# PLC1_3.net
KiCad netlist of a schematic drawn in Altium Designer
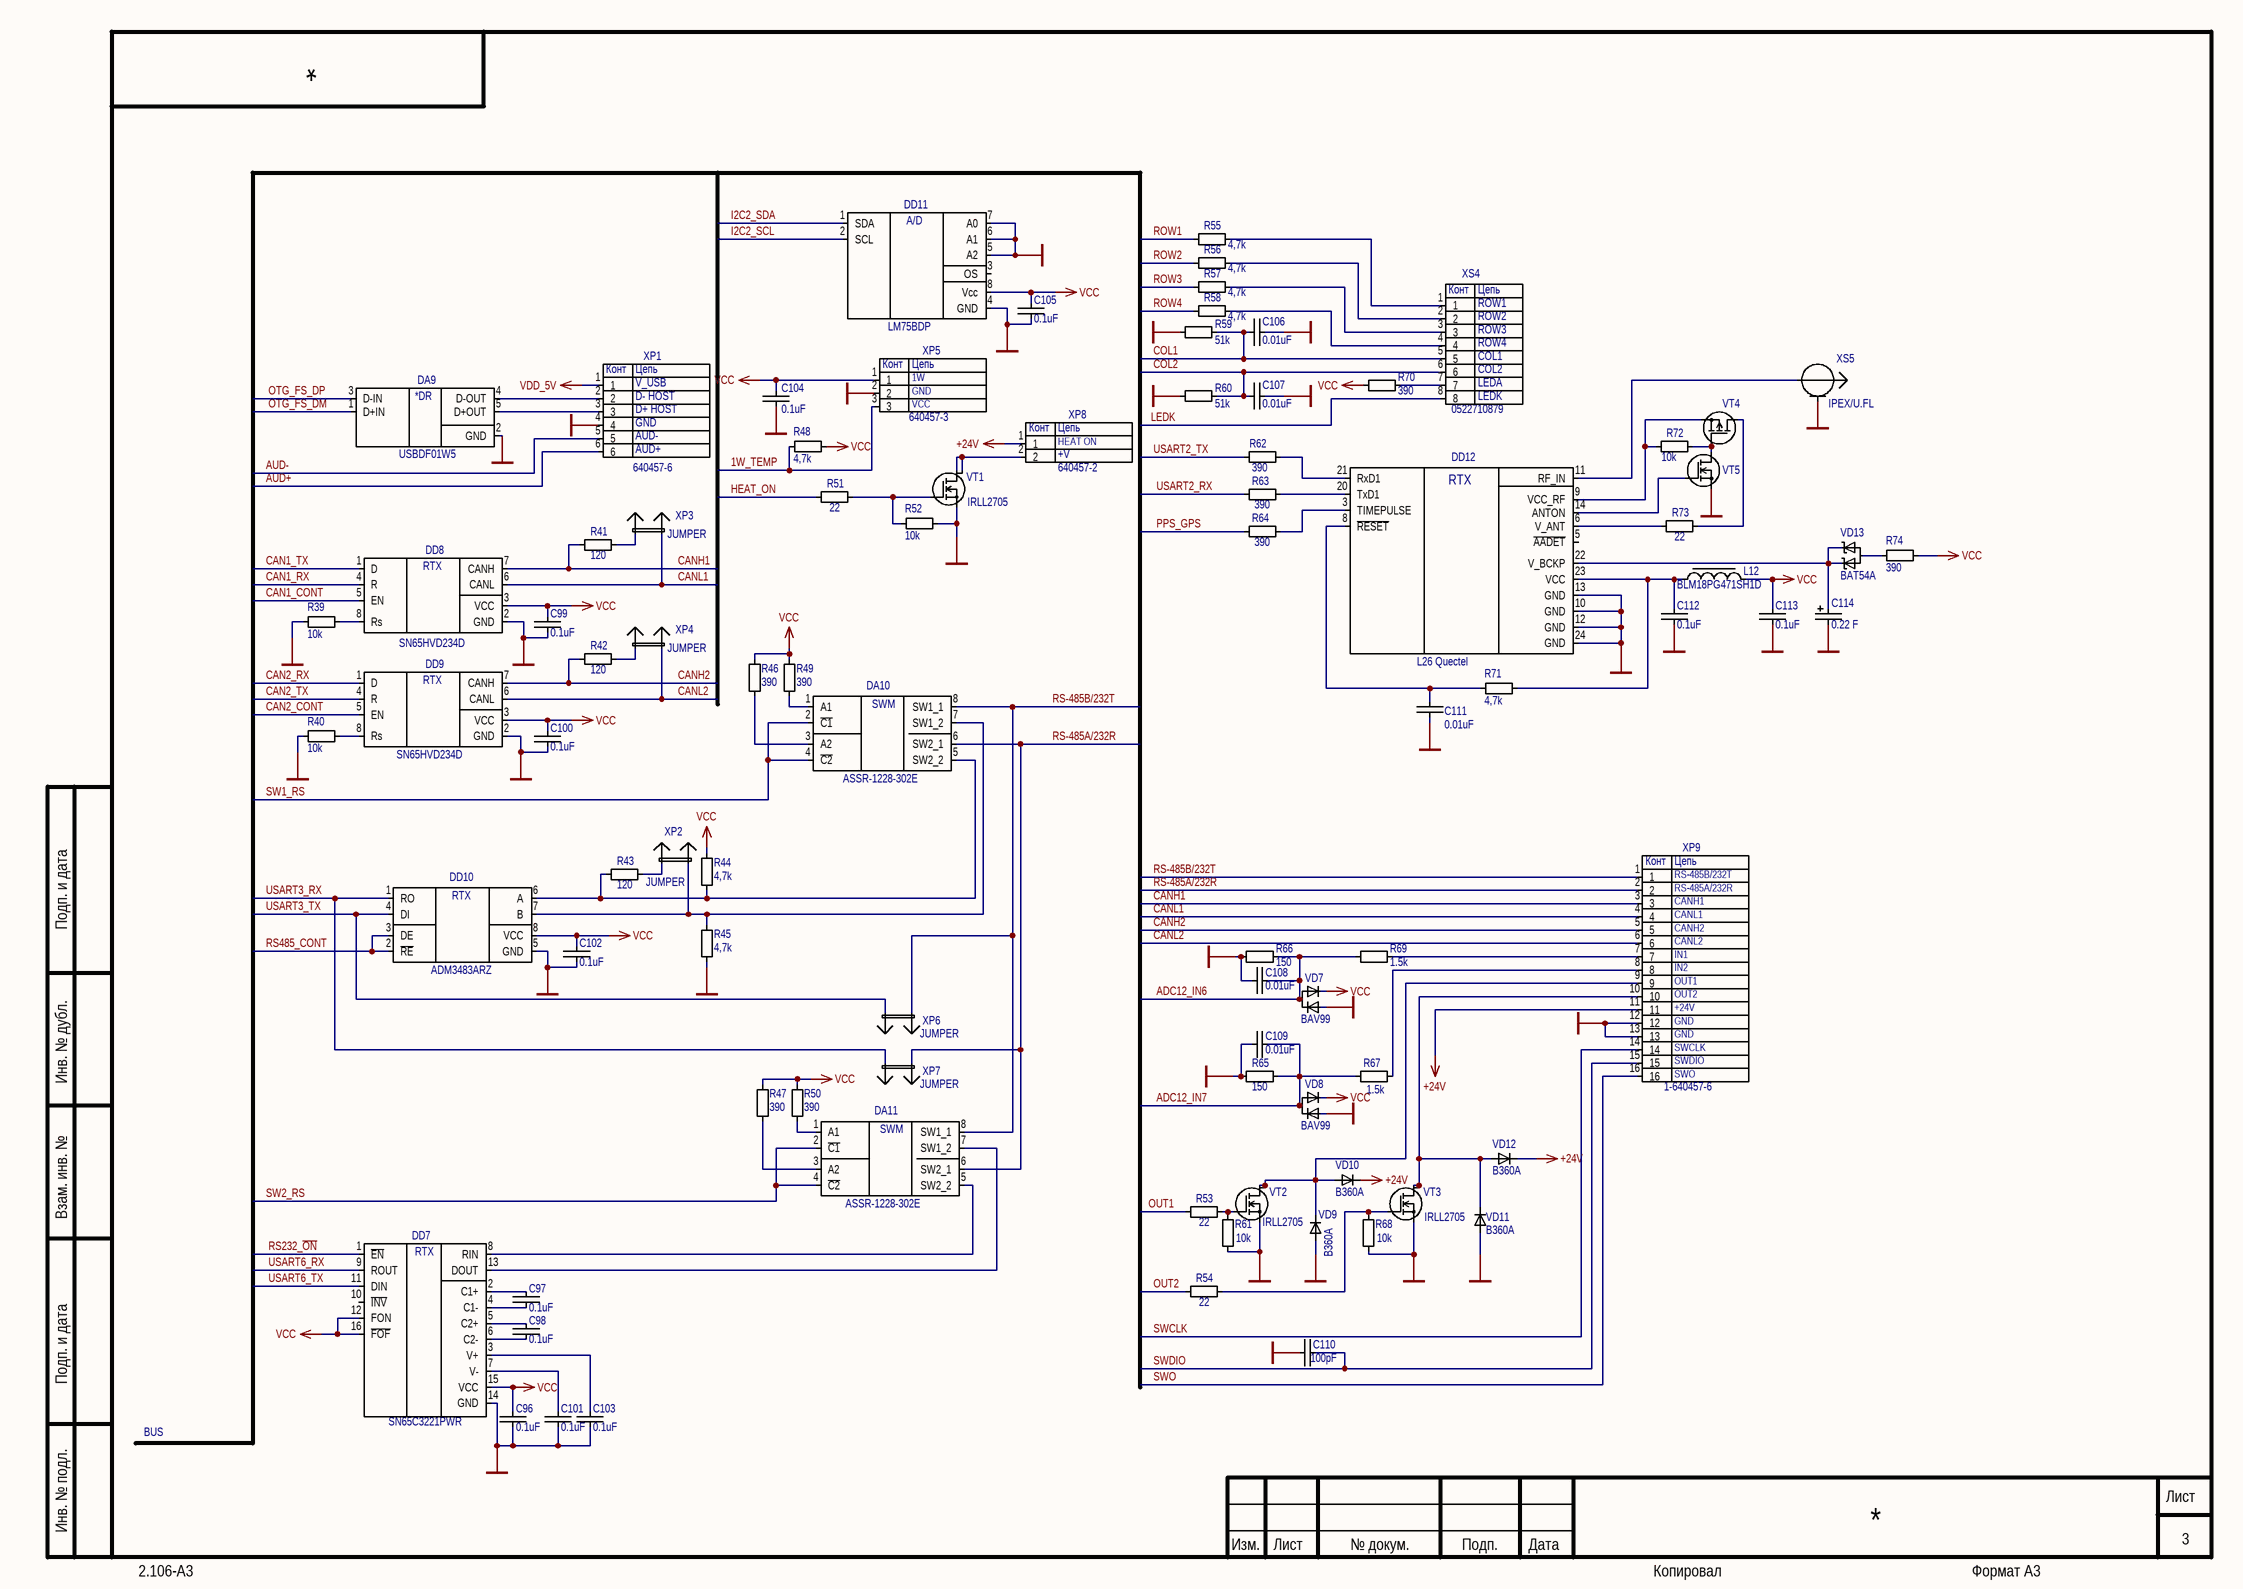
[diagram p0: PLC1_3.SchDoc]

(export (version "E")
  (design (tool "Eeschema 10.0.6"))
  (components
    (comp (ref "C96")
      (value "0.1uF")
      (footprint "CAP_0603")
      (fields (field (name "MANUFACTURER") "AVX") (field (name "PART NUMBER") "0603YC104KAT2A"))
      (libsource (lib "PLC1") (part "Cap_0603"))
    )
    (comp (ref "C97")
      (value "0.1uF")
      (footprint "CAP_0603")
      (fields (field (name "MANUFACTURER") "AVX") (field (name "PART NUMBER") "0603YC104KAT2A"))
      (libsource (lib "PLC1") (part "Cap_0603"))
    )
    (comp (ref "C98")
      (value "0.1uF")
      (footprint "CAP_0603")
      (fields (field (name "MANUFACTURER") "AVX") (field (name "PART NUMBER") "0603YC104KAT2A"))
      (libsource (lib "PLC1") (part "Cap_0603"))
    )
    (comp (ref "C99")
      (value "0.1uF")
      (footprint "CAP_0603")
      (fields (field (name "MANUFACTURER") "AVX") (field (name "PART NUMBER") "0603YC104KAT2A"))
      (libsource (lib "PLC1") (part "Cap_0603"))
    )
    (comp (ref "C100")
      (value "0.1uF")
      (footprint "CAP_0603")
      (fields (field (name "MANUFACTURER") "AVX") (field (name "PART NUMBER") "0603YC104KAT2A"))
      (libsource (lib "PLC1") (part "Cap_0603"))
    )
    (comp (ref "C101")
      (value "0.1uF")
      (footprint "CAP_0603")
      (fields (field (name "MANUFACTURER") "AVX") (field (name "PART NUMBER") "0603YC104KAT2A"))
      (libsource (lib "PLC1") (part "Cap_0603"))
    )
    (comp (ref "C102")
      (value "0.1uF")
      (footprint "CAP_0603")
      (fields (field (name "MANUFACTURER") "AVX") (field (name "PART NUMBER") "0603YC104KAT2A"))
      (libsource (lib "PLC1") (part "Cap_0603"))
    )
    (comp (ref "C103")
      (value "0.1uF")
      (footprint "CAP_0603")
      (fields (field (name "MANUFACTURER") "AVX") (field (name "PART NUMBER") "0603YC104KAT2A"))
      (libsource (lib "PLC1") (part "Cap_0603"))
    )
    (comp (ref "C104")
      (value "0.1uF")
      (footprint "CAP_0603")
      (fields (field (name "MANUFACTURER") "AVX") (field (name "PART NUMBER") "0603YC104KAT2A"))
      (libsource (lib "PLC1") (part "Cap_0603"))
    )
    (comp (ref "C105")
      (value "0.1uF")
      (footprint "CAP_0603")
      (fields (field (name "MANUFACTURER") "AVX") (field (name "PART NUMBER") "0603YC104KAT2A"))
      (libsource (lib "PLC1") (part "Cap_0603"))
    )
    (comp (ref "C106")
      (value "0.01uF")
      (footprint "CAP_0603")
      (fields (field (name "MANUFACTURER") "AVX") (field (name "PART NUMBER") "0603YC103KAT2A"))
      (libsource (lib "PLC1") (part "Cap_0603"))
    )
    (comp (ref "C107")
      (value "0.01uF")
      (footprint "CAP_0603")
      (fields (field (name "MANUFACTURER") "AVX") (field (name "PART NUMBER") "0603YC103KAT2A"))
      (libsource (lib "PLC1") (part "Cap_0603"))
    )
    (comp (ref "C108")
      (value "0.01uF")
      (footprint "CAP_0603")
      (fields (field (name "MANUFACTURER") "AVX") (field (name "PART NUMBER") "0603YC103KAT2A"))
      (libsource (lib "PLC1") (part "Cap_0603"))
    )
    (comp (ref "C109")
      (value "0.01uF")
      (footprint "CAP_0603")
      (fields (field (name "MANUFACTURER") "AVX") (field (name "PART NUMBER") "0603YC103KAT2A"))
      (libsource (lib "PLC1") (part "Cap_0603"))
    )
    (comp (ref "C110")
      (value "100pF")
      (footprint "CAP_0603")
      (fields
        (field (name "MANUFACTURER") "Yageo")
        (field (name "PART NUMBER") "CC0603JRNPO9BN101")
        (field (name "Comment") "100p")
      )
      (libsource (lib "PLC1") (part "Cap_0603"))
    )
    (comp (ref "C111")
      (value "0.01uF")
      (footprint "CAP_0603")
      (fields (field (name "MANUFACTURER") "AVX") (field (name "PART NUMBER") "0603YC103KAT2A"))
      (libsource (lib "PLC1") (part "Cap_0603"))
    )
    (comp (ref "C112")
      (value "0.1uF")
      (footprint "CAP_0603")
      (fields (field (name "MANUFACTURER") "AVX") (field (name "PART NUMBER") "0603YC104KAT2A"))
      (libsource (lib "PLC1") (part "Cap_0603"))
    )
    (comp (ref "C113")
      (value "0.1uF")
      (footprint "CAP_0603")
      (fields (field (name "MANUFACTURER") "AVX") (field (name "PART NUMBER") "0603YC104KAT2A"))
      (libsource (lib "PLC1") (part "Cap_0603"))
    )
    (comp (ref "C114")
      (value "0.22 F")
      (footprint "KR-5R5C104-R")
      (description "supercapacitor 0.22 uF")
      (fields (field (name "MANUFACTURER") "Panasonic") (field (name "PART NUMBER") "KR-5R5C224-R"))
      (libsource (lib "PLC1") (part "KR-5R5C104-R"))
    )
    (comp (ref "DA9")
      (value "USBDF01W5")
      (footprint "SOT323-5L")
      (description "Unidirectional 2 lines Filter + ESD")
      (fields (field (name "MANUFACTURER") "ST") (field (name "PART NUMBER") "USBDF01W5"))
      (libsource (lib "PLC1") (part "USBDF01W6"))
    )
    (comp (ref "DA10")
      (value "ASSR-1228-302E")
      (footprint "DIP8_GULL")
      (description "RS-485 PHY")
      (fields (field (name "MANUFACTURER") "AVAGO") (field (name "PART NUMBER") "ASSR-1228-302E"))
      (libsource (lib "PLC1") (part "ASSR-1228-302E"))
    )
    (comp (ref "DA11")
      (value "ASSR-1228-302E")
      (footprint "DIP8_GULL")
      (description "RS-485 PHY")
      (fields (field (name "MANUFACTURER") "AVAGO") (field (name "PART NUMBER") "ASSR-1228-302E"))
      (libsource (lib "PLC1") (part "ASSR-1228-302E"))
    )
    (comp (ref "DD7")
      (value "SN65C3221PWR")
      (footprint "TSSO5x6-G16")
      (description "RS-232 PHY CAN PHY")
      (fields (field (name "MANUFACTURER") "TI") (field (name "PART NUMBER") "SN65C3221PWR"))
      (libsource (lib "PLC1") (part "SN65C3221PWR"))
    )
    (comp (ref "DD8")
      (value "SN65HVD234D")
      (footprint "SOIC8")
      (description "SN65HVD234D CAN PHY")
      (fields (field (name "MANUFACTURER") "TI") (field (name "PART NUMBER") "SN65HVD234D"))
      (libsource (lib "PLC1") (part "SN65HVD234D"))
    )
    (comp (ref "DD9")
      (value "SN65HVD234D")
      (footprint "SOIC8")
      (description "SN65HVD234D CAN PHY")
      (fields (field (name "MANUFACTURER") "TI") (field (name "PART NUMBER") "SN65HVD234D"))
      (libsource (lib "PLC1") (part "SN65HVD234D"))
    )
    (comp (ref "DD10")
      (value "ADM3483")
      (footprint "SOIC8")
      (description "RS-485 PHY")
      (fields (field (name "MANUFACTURER") "Analog Devices") (field (name "PART NUMBER") "ADM3483ARZ"))
      (libsource (lib "PLC1") (part "ADM3483"))
    )
    (comp (ref "DD11")
      (value "LM75BDP")
      (footprint "TSSO3x5-G8/X.4")
      (description "LM75BDP TEMPERATURE SENSOR")
      (fields (field (name "MANUFACTURER") "NXP") (field (name "PART NUMBER") "LM75BDP"))
      (libsource (lib "PLC1") (part "LM75BDP"))
    )
    (comp (ref "DD12")
      (value "L26 Quectel")
      (footprint "VK1612U")
      (description "GPS receiver")
      (fields (field (name "MANUFACTURER") "Quectel") (field (name "PART NUMBER") "L26 Quectel"))
      (libsource (lib "PLC1") (part "L26 Quectel"))
    )
    (comp (ref "L12")
      (value "BLM18PG471SH1D")
      (footprint "R_IND_0603")
      (fields (field (name "MANUFACTURER") "Murata"))
      (libsource (lib "PLC1") (part "FCM1608KF-601T03"))
    )
    (comp (ref "R39")
      (value "10k")
      (footprint "RES_0603")
      (description "0603, 10k")
      (fields (field (name "MANUFACTURER") "Vishay") (field (name "PART NUMBER") "CRCW060310K0JNE"))
      (libsource (lib "PLC1") (part "Res_0603"))
    )
    (comp (ref "R40")
      (value "10k")
      (footprint "RES_0603")
      (description "0603, 10k")
      (fields (field (name "MANUFACTURER") "Vishay") (field (name "PART NUMBER") "CRCW060310K0JNE"))
      (libsource (lib "PLC1") (part "Res_0603"))
    )
    (comp (ref "R41")
      (value "120")
      (footprint "Res_2010")
      (description "2010")
      (fields
        (field (name "MANUFACTURER") "NIC Components Corp.")
        (field (name "PART NUMBER") "NRC50J121TRF")
      )
      (libsource (lib "PLC1") (part "Res_2010"))
    )
    (comp (ref "R42")
      (value "120")
      (footprint "Res_2010")
      (description "2010")
      (fields
        (field (name "MANUFACTURER") "NIC Components Corp.")
        (field (name "PART NUMBER") "NRC50J121TRF")
      )
      (libsource (lib "PLC1") (part "Res_2010"))
    )
    (comp (ref "R43")
      (value "120")
      (footprint "Res_2010")
      (description "2010")
      (fields
        (field (name "MANUFACTURER") "NIC Components Corp.")
        (field (name "PART NUMBER") "NRC50J121TRF")
      )
      (libsource (lib "PLC1") (part "Res_2010"))
    )
    (comp (ref "R44")
      (value "4,7k")
      (footprint "RES_0603")
      (description "0603, 100")
      (fields (field (name "MANUFACTURER") "Vishay") (field (name "PART NUMBER") "CRCW0603-472JRT1"))
      (libsource (lib "PLC1") (part "Res_0603"))
    )
    (comp (ref "R45")
      (value "4,7k")
      (footprint "RES_0603")
      (description "0603, 100")
      (fields (field (name "MANUFACTURER") "Vishay") (field (name "PART NUMBER") "CRCW0603-472JRT1"))
      (libsource (lib "PLC1") (part "Res_0603"))
    )
    (comp (ref "R46")
      (value "390")
      (footprint "RES_0603")
      (description "0603, 390")
      (fields (field (name "MANUFACTURER") "YAGEO") (field (name "PART NUMBER") "RC0603FR-07390RL"))
      (libsource (lib "PLC1") (part "Res_0603"))
    )
    (comp (ref "R47")
      (value "390")
      (footprint "RES_0603")
      (description "0603, 390")
      (fields (field (name "MANUFACTURER") "YAGEO") (field (name "PART NUMBER") "RC0603FR-07390RL"))
      (libsource (lib "PLC1") (part "Res_0603"))
    )
    (comp (ref "R48")
      (value "4,7k")
      (footprint "Res_0603")
      (description "0603, 100")
      (fields (field (name "MANUFACTURER") "Vishay") (field (name "PART NUMBER") "CRCW0603-472JRT1"))
      (libsource (lib "PLC1") (part "Res_0603"))
    )
    (comp (ref "R49")
      (value "390")
      (footprint "RES_0603")
      (description "0603, 390")
      (fields (field (name "MANUFACTURER") "YAGEO") (field (name "PART NUMBER") "RC0603FR-07390RL"))
      (libsource (lib "PLC1") (part "Res_0603"))
    )
    (comp (ref "R50")
      (value "390")
      (footprint "RES_0603")
      (description "0603, 390")
      (fields (field (name "MANUFACTURER") "YAGEO") (field (name "PART NUMBER") "RC0603FR-07390RL"))
      (libsource (lib "PLC1") (part "Res_0603"))
    )
    (comp (ref "R51")
      (value "22")
      (footprint "RES_0603")
      (description "0603, 22")
      (fields (field (name "MANUFACTURER") "Vishay") (field (name "PART NUMBER") "CRCW020122R0JNED"))
      (libsource (lib "PLC1") (part "Res_0603"))
    )
    (comp (ref "R52")
      (value "10k")
      (footprint "RES_0603")
      (description "0603, 10k")
      (fields (field (name "MANUFACTURER") "Vishay") (field (name "PART NUMBER") "CRCW060310K0JNE"))
      (libsource (lib "PLC1") (part "Res_0603"))
    )
    (comp (ref "R53")
      (value "22")
      (footprint "RES_0603")
      (description "0603, 22")
      (fields (field (name "MANUFACTURER") "Vishay") (field (name "PART NUMBER") "CRCW020122R0JNED"))
      (libsource (lib "PLC1") (part "Res_0603"))
    )
    (comp (ref "R54")
      (value "22")
      (footprint "RES_0603")
      (description "0603, 22")
      (fields (field (name "MANUFACTURER") "Vishay") (field (name "PART NUMBER") "CRCW020122R0JNED"))
      (libsource (lib "PLC1") (part "Res_0603"))
    )
    (comp (ref "R55")
      (value "4,7k")
      (footprint "Res_0603")
      (description "0603, 100")
      (fields (field (name "MANUFACTURER") "Vishay") (field (name "PART NUMBER") "CRCW0603-472JRT1"))
      (libsource (lib "PLC1") (part "Res_0603"))
    )
    (comp (ref "R56")
      (value "4,7k")
      (footprint "Res_0603")
      (description "0603, 100")
      (fields (field (name "MANUFACTURER") "Vishay") (field (name "PART NUMBER") "CRCW0603-472JRT1"))
      (libsource (lib "PLC1") (part "Res_0603"))
    )
    (comp (ref "R57")
      (value "4,7k")
      (footprint "Res_0603")
      (description "0603, 100")
      (fields (field (name "MANUFACTURER") "Vishay") (field (name "PART NUMBER") "CRCW0603-472JRT1"))
      (libsource (lib "PLC1") (part "Res_0603"))
    )
    (comp (ref "R58")
      (value "4,7k")
      (footprint "Res_0603")
      (description "0603, 100")
      (fields (field (name "MANUFACTURER") "Vishay") (field (name "PART NUMBER") "CRCW0603-472JRT1"))
      (libsource (lib "PLC1") (part "Res_0603"))
    )
    (comp (ref "R59")
      (value "51k")
      (footprint "RES_0603")
      (description "0603, 51k")
      (fields (field (name "MANUFACTURER") "Vishay") (field (name "PART NUMBER") "CRCW0603-513JRT1"))
      (libsource (lib "PLC1") (part "Res_0603"))
    )
    (comp (ref "R60")
      (value "51k")
      (footprint "RES_0603")
      (description "0603, 51k")
      (fields (field (name "MANUFACTURER") "Vishay") (field (name "PART NUMBER") "CRCW0603-513JRT1"))
      (libsource (lib "PLC1") (part "Res_0603"))
    )
    (comp (ref "R61")
      (value "10k")
      (footprint "RES_0603")
      (description "0603, 10k")
      (fields (field (name "MANUFACTURER") "Vishay") (field (name "PART NUMBER") "CRCW060310K0JNE"))
      (libsource (lib "PLC1") (part "Res_0603"))
    )
    (comp (ref "R62")
      (value "390")
      (footprint "RES_0603")
      (description "0603, 390")
      (fields (field (name "MANUFACTURER") "YAGEO") (field (name "PART NUMBER") "RC0603FR-07390RL"))
      (libsource (lib "PLC1") (part "Res_0603"))
    )
    (comp (ref "R63")
      (value "390")
      (footprint "RES_0603")
      (description "0603, 390")
      (fields (field (name "MANUFACTURER") "YAGEO") (field (name "PART NUMBER") "RC0603FR-07390RL"))
      (libsource (lib "PLC1") (part "Res_0603"))
    )
    (comp (ref "R64")
      (value "390")
      (footprint "RES_0603")
      (description "0603, 390")
      (fields (field (name "MANUFACTURER") "YAGEO") (field (name "PART NUMBER") "RC0603FR-07390RL"))
      (libsource (lib "PLC1") (part "Res_0603"))
    )
    (comp (ref "R65")
      (value "150")
      (footprint "Res_1206")
      (fields
        (field (name "MANUFACTURER") "Vishay")
        (field (name "PART NUMBER") "CRCW1206150RFKEA")
        (field (name "Comment") "Res_1206")
      )
      (libsource (lib "PLC1") (part "Res_1206"))
    )
    (comp (ref "R66")
      (value "150")
      (footprint "Res_1206")
      (fields
        (field (name "MANUFACTURER") "Vishay")
        (field (name "PART NUMBER") "CRCW1206150RFKEA")
        (field (name "Comment") "Res_1206")
      )
      (libsource (lib "PLC1") (part "Res_1206"))
    )
    (comp (ref "R67")
      (value "1.5k")
      (footprint "Res_1206")
      (fields
        (field (name "MANUFACTURER") "Vishay")
        (field (name "PART NUMBER") "CRCW12061K50FKEA")
        (field (name "Comment") "Res_1206")
      )
      (libsource (lib "PLC1") (part "Res_1206"))
    )
    (comp (ref "R68")
      (value "10k")
      (footprint "RES_0603")
      (description "0603, 10k")
      (fields (field (name "MANUFACTURER") "Vishay") (field (name "PART NUMBER") "CRCW060310K0JNE"))
      (libsource (lib "PLC1") (part "Res_0603"))
    )
    (comp (ref "R69")
      (value "1.5k")
      (footprint "Res_1206")
      (fields
        (field (name "MANUFACTURER") "Vishay")
        (field (name "PART NUMBER") "CRCW12061K50FKEA")
        (field (name "Comment") "Res_1206")
      )
      (libsource (lib "PLC1") (part "Res_1206"))
    )
    (comp (ref "R70")
      (value "390")
      (footprint "RES_0603")
      (description "0603, 390")
      (fields (field (name "MANUFACTURER") "YAGEO") (field (name "PART NUMBER") "RC0603FR-07390RL"))
      (libsource (lib "PLC1") (part "Res_0603"))
    )
    (comp (ref "R71")
      (value "4,7k")
      (footprint "Res_0603")
      (description "0603, 100")
      (fields (field (name "MANUFACTURER") "Vishay") (field (name "PART NUMBER") "CRCW0603-472JRT1"))
      (libsource (lib "PLC1") (part "Res_0603"))
    )
    (comp (ref "R72")
      (value "10k")
      (footprint "RES_0603")
      (description "0603, 10k")
      (fields (field (name "MANUFACTURER") "Vishay") (field (name "PART NUMBER") "CRCW060310K0JNE"))
      (libsource (lib "PLC1") (part "Res_0603"))
    )
    (comp (ref "R73")
      (value "22")
      (footprint "RES_0603")
      (description "0603, 22")
      (fields (field (name "MANUFACTURER") "Vishay") (field (name "PART NUMBER") "CRCW020122R0JNED"))
      (libsource (lib "PLC1") (part "Res_0603"))
    )
    (comp (ref "R74")
      (value "390")
      (footprint "RES_0603")
      (description "0603, 390")
      (fields (field (name "MANUFACTURER") "YAGEO") (field (name "PART NUMBER") "RC0603FR-07390RL"))
      (libsource (lib "PLC1") (part "Res_0603"))
    )
    (comp (ref "VD7")
      (value "BAV99")
      (footprint "SOT-23")
      (fields (field (name "MANUFACTURER") "Fairchild"))
      (libsource (lib "PLC1") (part "BAV99"))
    )
    (comp (ref "VD8")
      (value "BAV99")
      (footprint "SOT-23")
      (fields (field (name "MANUFACTURER") "Fairchild"))
      (libsource (lib "PLC1") (part "BAV99"))
    )
    (comp (ref "VD9")
      (value "B360A")
      (footprint "DO-214AC")
      (fields (field (name "PART NUMBER") "B360A") (field (name "MANUFACTURER") "VISHAY"))
      (libsource (lib "PLC1") (part "S1A"))
    )
    (comp (ref "VD10")
      (value "B360A")
      (footprint "DO-214AC")
      (fields (field (name "PART NUMBER") "B360A") (field (name "MANUFACTURER") "VISHAY"))
      (libsource (lib "") (part "S1A_1"))
    )
    (comp (ref "VD11")
      (value "B360A")
      (footprint "DO-214AC")
      (fields (field (name "PART NUMBER") "B360A") (field (name "MANUFACTURER") "VISHAY"))
      (libsource (lib "PLC1") (part "S1A"))
    )
    (comp (ref "VD12")
      (value "B360A")
      (footprint "DO-214AC")
      (fields (field (name "PART NUMBER") "B360A") (field (name "MANUFACTURER") "VISHAY"))
      (libsource (lib "PLC1") (part "S1A"))
    )
    (comp (ref "VD13") (value "BAT54A") (footprint "SOT-23") (libsource (lib "PLC1") (part "BAT54A")))
    (comp (ref "VT1")
      (value "N-CHAN_SOT-223")
      (footprint "SOT-223")
      (fields (field (name "PART NUMBER") "IRLL2705"))
      (libsource (lib "PLC1") (part "N-CHAN_SOT-223"))
    )
    (comp (ref "VT2")
      (value "N-CHAN_SOT-223")
      (footprint "SOT-223")
      (fields (field (name "PART NUMBER") "IRLL2705"))
      (libsource (lib "PLC1") (part "N-CHAN_SOT-223"))
    )
    (comp (ref "VT3")
      (value "N-CHAN_SOT-223")
      (footprint "SOT-223")
      (fields (field (name "PART NUMBER") "IRLL2705"))
      (libsource (lib "PLC1") (part "N-CHAN_SOT-223"))
    )
    (comp (ref "VT4")
      (value "IRLML6402")
      (footprint "SOT-23")
      (libsource (lib "PLC1") (part "P-CHAN_SOT-23"))
    )
    (comp (ref "VT5")
      (value "N-CHAN_SOT-23")
      (footprint "SOT-23")
      (fields (field (name "MANUFACTURER") "IR") (field (name "PART NUMBER") "IRLML2502"))
      (libsource (lib "PLC1") (part "N-CHAN_SOT-23"))
    )
    (comp (ref "XP1")
      (value "640457-6")
      (footprint "640457-6")
      (fields (field (name "MANUFACTURER") "TE"))
      (libsource (lib "PLC1") (part "640457-6"))
    )
    (comp (ref "XP2")
      (value "JUMPER")
      (footprint "PLS2-R")
      (description "JUMPER 2.54")
      (fields (field (name "MANUFACTURER") "TE") (field (name "PART NUMBER") "PLS-2R"))
      (libsource (lib "PLC1") (part "PLS-2 R"))
    )
    (comp (ref "XP3")
      (value "JUMPER")
      (footprint "PLS2-R")
      (description "JUMPER 2.54")
      (fields (field (name "MANUFACTURER") "TE") (field (name "PART NUMBER") "PLS-2R"))
      (libsource (lib "PLC1") (part "PLS-2 R"))
    )
    (comp (ref "XP4")
      (value "JUMPER")
      (footprint "PLS2-R")
      (description "JUMPER 2.54")
      (fields (field (name "MANUFACTURER") "TE") (field (name "PART NUMBER") "PLS-2R"))
      (libsource (lib "PLC1") (part "PLS-2 R"))
    )
    (comp (ref "XP5")
      (value "640457-3")
      (footprint "640457-3")
      (fields (field (name "MANUFACTURER") "TE"))
      (libsource (lib "PLC1") (part "640457-3"))
    )
    (comp (ref "XP6")
      (value "JUMPER")
      (footprint "JMPTOPOLOGY")
      (description "JUMPER 2.54")
      (fields (field (name "MANUFACTURER") "TE"))
      (libsource (lib "PLC1") (part "TOPOLOGYJMP"))
    )
    (comp (ref "XP7")
      (value "JUMPER")
      (footprint "JMPTOPOLOGY")
      (description "JUMPER 2.54")
      (fields (field (name "MANUFACTURER") "TE"))
      (libsource (lib "PLC1") (part "TOPOLOGYJMP"))
    )
    (comp (ref "XP8")
      (value "640457-2")
      (footprint "640457-2")
      (fields (field (name "MANUFACTURER") "TE"))
      (libsource (lib "PLC1") (part "640457-2"))
    )
    (comp (ref "XP9")
      (value "1-640457-6")
      (footprint "1-640457-6")
      (fields (field (name "MANUFACTURER") "TE"))
      (libsource (lib "PLC1") (part "1-640457-6"))
    )
    (comp (ref "XS4")
      (value "0522710879")
      (footprint "0522710879")
      (fields (field (name "MANUFACTURER") "Molex"))
      (libsource (lib "PLC1") (part "0522710879"))
    )
    (comp (ref "XS5")
      (value "IPEX/U.FL")
      (footprint "IPEX MHFI")
      (description "IPEX/U.FL male pcb SMT")
      (fields
        (field (name "MANUFACTURER") "taoglas limited")
        (field (name "PACKAGEREFERENCE") "IPEX/U.FL")
        (field (name "PART NUMBER") "20279-001E-01")
      )
      (libsource (lib "PLC1") (part "IPEX/U.FL"))
    )
  )
  (nets
    (net (code "1") (name "+24V") (class "Default")
      (node (ref "VD10") (pin "2") (pinfunction "2_2") (pintype "passive"))
      (node (ref "VD12") (pin "2") (pinfunction "2_2") (pintype "passive"))
      (node (ref "XP8") (pin "1") (pinfunction "1_1") (pintype "passive"))
      (node (ref "XP9") (pin "11") (pinfunction "11_11") (pintype "passive"))
    )
    (net (code "2") (name "/1W_TEMP") (class "Default")
      (node (ref "R48") (pin "2") (pinfunction "2_2") (pintype "passive"))
      (node (ref "XP5") (pin "3") (pinfunction "3_3") (pintype "passive"))
    )
    (net (code "3") (name "/ADC12_IN6") (class "Default")
      (node (ref "C108") (pin "2") (pinfunction "2_2") (pintype "passive"))
      (node (ref "R66") (pin "1") (pinfunction "1_1") (pintype "passive"))
      (node (ref "R69") (pin "2") (pinfunction "2_2") (pintype "passive"))
      (node (ref "VD7") (pin "3") (pinfunction "3_3") (pintype "passive"))
    )
    (net (code "4") (name "/ADC12_IN7") (class "Default")
      (node (ref "C109") (pin "2") (pinfunction "2_2") (pintype "passive"))
      (node (ref "R65") (pin "1") (pinfunction "1_1") (pintype "passive"))
      (node (ref "R67") (pin "2") (pinfunction "2_2") (pintype "passive"))
      (node (ref "VD8") (pin "3") (pinfunction "3_3") (pintype "passive"))
    )
    (net (code "5") (name "/AUD+") (class "Default")
      (node (ref "XP1") (pin "6") (pinfunction "6_6") (pintype "passive"))
    )
    (net (code "6") (name "/AUD-") (class "Default")
      (node (ref "XP1") (pin "5") (pinfunction "5_5") (pintype "passive"))
    )
    (net (code "7") (name "/CAN1_CONT") (class "Default")
      (node (ref "DD8") (pin "5") (pinfunction "EN_5") (pintype "passive"))
    )
    (net (code "8") (name "/CAN1_RX") (class "Default")
      (node (ref "DD8") (pin "4") (pinfunction "R_4") (pintype "passive"))
    )
    (net (code "9") (name "/CAN1_TX") (class "Default")
      (node (ref "DD8") (pin "1") (pinfunction "D_1") (pintype "passive"))
    )
    (net (code "10") (name "/CAN2_CONT") (class "Default")
      (node (ref "DD9") (pin "5") (pinfunction "EN_5") (pintype "passive"))
    )
    (net (code "11") (name "/CAN2_RX") (class "Default")
      (node (ref "DD9") (pin "1") (pinfunction "D_1") (pintype "passive"))
    )
    (net (code "12") (name "/CAN2_TX") (class "Default")
      (node (ref "DD9") (pin "4") (pinfunction "R_4") (pintype "passive"))
    )
    (net (code "13") (name "/CANH1") (class "Default")
      (node (ref "DD8") (pin "7") (pinfunction "CANH_7") (pintype "passive"))
      (node (ref "R41") (pin "1") (pinfunction "1_1") (pintype "passive"))
      (node (ref "XP9") (pin "3") (pinfunction "3_3") (pintype "passive"))
    )
    (net (code "14") (name "/CANH2") (class "Default")
      (node (ref "DD9") (pin "7") (pinfunction "CANH_7") (pintype "passive"))
      (node (ref "R42") (pin "1") (pinfunction "1_1") (pintype "passive"))
      (node (ref "XP9") (pin "5") (pinfunction "5_5") (pintype "passive"))
    )
    (net (code "15") (name "/CANL1") (class "Default")
      (node (ref "DD8") (pin "6") (pinfunction "CANL_6") (pintype "passive"))
      (node (ref "XP3") (pin "2") (pinfunction "2_2") (pintype "passive"))
      (node (ref "XP9") (pin "4") (pinfunction "4_4") (pintype "passive"))
    )
    (net (code "16") (name "/CANL2") (class "Default")
      (node (ref "DD9") (pin "6") (pinfunction "CANL_6") (pintype "passive"))
      (node (ref "XP4") (pin "2") (pinfunction "2_2") (pintype "passive"))
      (node (ref "XP9") (pin "6") (pinfunction "6_6") (pintype "passive"))
    )
    (net (code "17") (name "/COL1") (class "Default")
      (node (ref "C106") (pin "2") (pinfunction "2_2") (pintype "passive"))
      (node (ref "R59") (pin "1") (pinfunction "1_1") (pintype "passive"))
      (node (ref "XS4") (pin "5") (pinfunction "5_5") (pintype "passive"))
    )
    (net (code "18") (name "/COL2") (class "Default")
      (node (ref "C107") (pin "2") (pinfunction "2_2") (pintype "passive"))
      (node (ref "R60") (pin "1") (pinfunction "1_1") (pintype "passive"))
      (node (ref "XS4") (pin "6") (pinfunction "6_6") (pintype "passive"))
    )
    (net (code "19") (name "/HEAT_ON") (class "Default")
      (node (ref "R51") (pin "1") (pinfunction "1_1") (pintype "passive"))
    )
    (net (code "20") (name "/I2C2_SCL") (class "Default")
      (node (ref "DD11") (pin "2") (pinfunction "SCL_2") (pintype "passive"))
    )
    (net (code "21") (name "/I2C2_SDA") (class "Default")
      (node (ref "DD11") (pin "1") (pinfunction "SDA_1") (pintype "passive"))
    )
    (net (code "22") (name "/LEDK") (class "Default")
      (node (ref "XS4") (pin "8") (pinfunction "8_8") (pintype "passive"))
    )
    (net (code "23") (name "/OTG_FS_DM") (class "Default")
      (node (ref "DA9") (pin "1") (pinfunction "D+IN_1") (pintype "passive"))
    )
    (net (code "24") (name "/OTG_FS_DP") (class "Default")
      (node (ref "DA9") (pin "3") (pinfunction "D-IN_3") (pintype "passive"))
    )
    (net (code "25") (name "/OUT1") (class "Default")
      (node (ref "R53") (pin "1") (pinfunction "1_1") (pintype "passive"))
    )
    (net (code "26") (name "/OUT2") (class "Default")
      (node (ref "R54") (pin "1") (pinfunction "1_1") (pintype "passive"))
    )
    (net (code "27") (name "/PPS_GPS") (class "Default")
      (node (ref "R64") (pin "1") (pinfunction "1_1") (pintype "passive"))
    )
    (net (code "28") (name "/ROW1") (class "Default")
      (node (ref "R55") (pin "2") (pinfunction "2_2") (pintype "passive"))
    )
    (net (code "29") (name "/ROW2") (class "Default")
      (node (ref "R56") (pin "2") (pinfunction "2_2") (pintype "passive"))
    )
    (net (code "30") (name "/ROW3") (class "Default")
      (node (ref "R57") (pin "2") (pinfunction "2_2") (pintype "passive"))
    )
    (net (code "31") (name "/ROW4") (class "Default")
      (node (ref "R58") (pin "2") (pinfunction "2_2") (pintype "passive"))
    )
    (net (code "32") (name "/RS-485A{slash}232R") (class "Default")
      (node (ref "DA10") (pin "6") (pinfunction "SW2_1_6") (pintype "passive"))
      (node (ref "DA11") (pin "6") (pinfunction "SW2_1_6") (pintype "passive"))
      (node (ref "XP7") (pin "1") (pinfunction "1_1") (pintype "passive"))
      (node (ref "XP9") (pin "2") (pinfunction "2_2") (pintype "passive"))
    )
    (net (code "33") (name "/RS-485B{slash}232T") (class "Default")
      (node (ref "DA10") (pin "8") (pinfunction "SW1_1_8") (pintype "passive"))
      (node (ref "DA11") (pin "8") (pinfunction "SW1_1_8") (pintype "passive"))
      (node (ref "XP6") (pin "1") (pinfunction "1_1") (pintype "passive"))
      (node (ref "XP9") (pin "1") (pinfunction "1_1") (pintype "passive"))
    )
    (net (code "34") (name "/RS232_~{ON}") (class "Default")
      (node (ref "DD7") (pin "1") (pinfunction "~{EN}_1") (pintype "passive"))
    )
    (net (code "35") (name "/RS485_CONT") (class "Default")
      (node (ref "DD10") (pin "2") (pinfunction "~{RE}_2") (pintype "passive"))
      (node (ref "DD10") (pin "3") (pinfunction "DE_3") (pintype "passive"))
    )
    (net (code "36") (name "/SW1_RS") (class "Default")
      (node (ref "DA10") (pin "2") (pinfunction "~{C1}_2") (pintype "passive"))
      (node (ref "DA10") (pin "4") (pinfunction "~{C2}_4") (pintype "passive"))
    )
    (net (code "37") (name "/SW2_RS") (class "Default")
      (node (ref "DA11") (pin "2") (pinfunction "~{C1}_2") (pintype "passive"))
      (node (ref "DA11") (pin "4") (pinfunction "~{C2}_4") (pintype "passive"))
    )
    (net (code "38") (name "/SWCLK") (class "Default")
      (node (ref "XP9") (pin "14") (pinfunction "14_14") (pintype "passive"))
    )
    (net (code "39") (name "/SWDIO") (class "Default")
      (node (ref "C110") (pin "1") (pinfunction "1_1") (pintype "passive"))
      (node (ref "XP9") (pin "15") (pinfunction "15_15") (pintype "passive"))
    )
    (net (code "40") (name "/SWO") (class "Default")
      (node (ref "XP9") (pin "16") (pinfunction "16_16") (pintype "passive"))
    )
    (net (code "41") (name "/USART2_RX") (class "Default")
      (node (ref "R63") (pin "1") (pinfunction "1_1") (pintype "passive"))
    )
    (net (code "42") (name "/USART2_TX") (class "Default")
      (node (ref "R62") (pin "1") (pinfunction "1_1") (pintype "passive"))
    )
    (net (code "43") (name "/USART3_RX") (class "Default")
      (node (ref "DD10") (pin "1") (pinfunction "RO_1") (pintype "passive"))
      (node (ref "XP7") (pin "2") (pinfunction "2_2") (pintype "passive"))
    )
    (net (code "44") (name "/USART3_TX") (class "Default")
      (node (ref "DD10") (pin "4") (pinfunction "DI_4") (pintype "passive"))
      (node (ref "XP6") (pin "2") (pinfunction "2_2") (pintype "passive"))
    )
    (net (code "45") (name "/USART6_RX") (class "Default")
      (node (ref "DD7") (pin "9") (pinfunction "ROUT_9") (pintype "passive"))
    )
    (net (code "46") (name "/USART6_TX") (class "Default")
      (node (ref "DD7") (pin "11") (pinfunction "DIN_11") (pintype "passive"))
    )
    (net (code "47") (name "GND") (class "Default")
      (node (ref "C100") (pin "2") (pinfunction "2_2") (pintype "passive"))
      (node (ref "C101") (pin "2") (pinfunction "2_2") (pintype "passive"))
      (node (ref "C102") (pin "2") (pinfunction "2_2") (pintype "passive"))
      (node (ref "C103") (pin "2") (pinfunction "2_2") (pintype "passive"))
      (node (ref "C104") (pin "2") (pinfunction "2_2") (pintype "passive"))
      (node (ref "C105") (pin "2") (pinfunction "2_2") (pintype "passive"))
      (node (ref "C106") (pin "1") (pinfunction "1_1") (pintype "passive"))
      (node (ref "C107") (pin "1") (pinfunction "1_1") (pintype "passive"))
      (node (ref "C108") (pin "1") (pinfunction "1_1") (pintype "passive"))
      (node (ref "C109") (pin "1") (pinfunction "1_1") (pintype "passive"))
      (node (ref "C110") (pin "2") (pinfunction "2_2") (pintype "passive"))
      (node (ref "C111") (pin "2") (pinfunction "2_2") (pintype "passive"))
      (node (ref "C112") (pin "2") (pinfunction "2_2") (pintype "passive"))
      (node (ref "C113") (pin "2") (pinfunction "2_2") (pintype "passive"))
      (node (ref "C114") (pin "2") (pinfunction "2_2") (pintype "passive"))
      (node (ref "C96") (pin "2") (pinfunction "2_2") (pintype "passive"))
      (node (ref "C99") (pin "2") (pinfunction "2_2") (pintype "passive"))
      (node (ref "DA9") (pin "2") (pinfunction "GND_2") (pintype "passive"))
      (node (ref "DD10") (pin "5") (pinfunction "GND_5") (pintype "passive"))
      (node (ref "DD11") (pin "4") (pinfunction "GND_4") (pintype "passive"))
      (node (ref "DD11") (pin "5") (pinfunction "A2_5") (pintype "passive"))
      (node (ref "DD11") (pin "6") (pinfunction "A1_6") (pintype "passive"))
      (node (ref "DD11") (pin "7") (pinfunction "A0_7") (pintype "passive"))
      (node (ref "DD12") (pin "10") (pinfunction "GND_10") (pintype "passive"))
      (node (ref "DD12") (pin "12") (pinfunction "GND_12") (pintype "passive"))
      (node (ref "DD12") (pin "13") (pinfunction "GND_13") (pintype "passive"))
      (node (ref "DD12") (pin "24") (pinfunction "GND_24") (pintype "passive"))
      (node (ref "DD7") (pin "14") (pinfunction "GND_14") (pintype "passive"))
      (node (ref "DD8") (pin "2") (pinfunction "GND_2") (pintype "passive"))
      (node (ref "DD9") (pin "2") (pinfunction "GND_2") (pintype "passive"))
      (node (ref "R39") (pin "2") (pinfunction "2_2") (pintype "passive"))
      (node (ref "R40") (pin "2") (pinfunction "2_2") (pintype "passive"))
      (node (ref "R45") (pin "2") (pinfunction "2_2") (pintype "passive"))
      (node (ref "R52") (pin "1") (pinfunction "1_1") (pintype "passive"))
      (node (ref "R59") (pin "2") (pinfunction "2_2") (pintype "passive"))
      (node (ref "R60") (pin "2") (pinfunction "2_2") (pintype "passive"))
      (node (ref "R61") (pin "1") (pinfunction "1_1") (pintype "passive"))
      (node (ref "R65") (pin "2") (pinfunction "2_2") (pintype "passive"))
      (node (ref "R66") (pin "2") (pinfunction "2_2") (pintype "passive"))
      (node (ref "R68") (pin "1") (pinfunction "1_1") (pintype "passive"))
      (node (ref "VD11") (pin "1") (pinfunction "1_1") (pintype "passive"))
      (node (ref "VD7") (pin "1") (pinfunction "1_1") (pintype "passive"))
      (node (ref "VD8") (pin "1") (pinfunction "1_1") (pintype "passive"))
      (node (ref "VD9") (pin "1") (pinfunction "1_1") (pintype "passive"))
      (node (ref "VT1") (pin "3") (pinfunction "3_3") (pintype "passive"))
      (node (ref "VT2") (pin "3") (pinfunction "3_3") (pintype "passive"))
      (node (ref "VT3") (pin "3") (pinfunction "3_3") (pintype "passive"))
      (node (ref "VT5") (pin "2") (pinfunction "2_2") (pintype "passive"))
      (node (ref "XP1") (pin "4") (pinfunction "4_4") (pintype "passive"))
      (node (ref "XP5") (pin "2") (pinfunction "2_2") (pintype "passive"))
      (node (ref "XP9") (pin "12") (pinfunction "12_12") (pintype "passive"))
      (node (ref "XP9") (pin "13") (pinfunction "13_13") (pintype "passive"))
      (node (ref "XS5") (pin "2") (pinfunction "2_2") (pintype "passive"))
    )
    (net (code "48") (name "Net-(DA9-D+OUT)") (class "Default")
      (node (ref "DA9") (pin "5") (pinfunction "D+OUT_5") (pintype "passive"))
      (node (ref "XP1") (pin "3") (pinfunction "3_3") (pintype "passive"))
    )
    (net (code "49") (name "Net-(DA9-D-OUT)") (class "Default")
      (node (ref "DA9") (pin "4") (pinfunction "D-OUT_4") (pintype "passive"))
      (node (ref "XP1") (pin "2") (pinfunction "2_2") (pintype "passive"))
    )
    (net (code "50") (name "Net-(DA10-A1)") (class "Default")
      (node (ref "DA10") (pin "1") (pinfunction "A1_1") (pintype "passive"))
      (node (ref "R49") (pin "2") (pinfunction "2_2") (pintype "passive"))
    )
    (net (code "51") (name "Net-(DA10-A2)") (class "Default")
      (node (ref "DA10") (pin "3") (pinfunction "A2_3") (pintype "passive"))
      (node (ref "R46") (pin "2") (pinfunction "2_2") (pintype "passive"))
    )
    (net (code "52") (name "Net-(DA10-SW1_2)") (class "Default")
      (node (ref "DA10") (pin "7") (pinfunction "SW1_2_7") (pintype "passive"))
      (node (ref "DD10") (pin "7") (pinfunction "B_7") (pintype "passive"))
      (node (ref "R45") (pin "1") (pinfunction "1_1") (pintype "passive"))
      (node (ref "XP2") (pin "2") (pinfunction "2_2") (pintype "passive"))
    )
    (net (code "53") (name "Net-(DA10-SW2_2)") (class "Default")
      (node (ref "DA10") (pin "5") (pinfunction "SW2_2_5") (pintype "passive"))
      (node (ref "DD10") (pin "6") (pinfunction "A_6") (pintype "passive"))
      (node (ref "R43") (pin "1") (pinfunction "1_1") (pintype "passive"))
      (node (ref "R44") (pin "2") (pinfunction "2_2") (pintype "passive"))
    )
    (net (code "54") (name "Net-(DA11-A1)") (class "Default")
      (node (ref "DA11") (pin "1") (pinfunction "A1_1") (pintype "passive"))
      (node (ref "R50") (pin "2") (pinfunction "2_2") (pintype "passive"))
    )
    (net (code "55") (name "Net-(DA11-A2)") (class "Default")
      (node (ref "DA11") (pin "3") (pinfunction "A2_3") (pintype "passive"))
      (node (ref "R47") (pin "2") (pinfunction "2_2") (pintype "passive"))
    )
    (net (code "56") (name "Net-(DA11-SW1_2)") (class "Default")
      (node (ref "DA11") (pin "7") (pinfunction "SW1_2_7") (pintype "passive"))
      (node (ref "DD7") (pin "13") (pinfunction "DOUT_13") (pintype "passive"))
    )
    (net (code "57") (name "Net-(DA11-SW2_2)") (class "Default")
      (node (ref "DA11") (pin "5") (pinfunction "SW2_2_5") (pintype "passive"))
      (node (ref "DD7") (pin "8") (pinfunction "RIN_8") (pintype "passive"))
    )
    (net (code "58") (name "Net-(DD7-C1+)") (class "Default")
      (node (ref "C97") (pin "1") (pinfunction "1_1") (pintype "passive"))
      (node (ref "DD7") (pin "2") (pinfunction "C1+_2") (pintype "passive"))
    )
    (net (code "59") (name "Net-(DD7-C1-)") (class "Default")
      (node (ref "C97") (pin "2") (pinfunction "2_2") (pintype "passive"))
      (node (ref "DD7") (pin "4") (pinfunction "C1-_4") (pintype "passive"))
    )
    (net (code "60") (name "Net-(DD7-C2+)") (class "Default")
      (node (ref "C98") (pin "1") (pinfunction "1_1") (pintype "passive"))
      (node (ref "DD7") (pin "5") (pinfunction "C2+_5") (pintype "passive"))
    )
    (net (code "61") (name "Net-(DD7-C2-)") (class "Default")
      (node (ref "C98") (pin "2") (pinfunction "2_2") (pintype "passive"))
      (node (ref "DD7") (pin "6") (pinfunction "C2-_6") (pintype "passive"))
    )
    (net (code "62") (name "Net-(DD7-V+)") (class "Default")
      (node (ref "C103") (pin "1") (pinfunction "1_1") (pintype "passive"))
      (node (ref "DD7") (pin "3") (pinfunction "V+_3") (pintype "passive"))
    )
    (net (code "63") (name "Net-(DD7-V-)") (class "Default")
      (node (ref "C101") (pin "1") (pinfunction "1_1") (pintype "passive"))
      (node (ref "DD7") (pin "7") (pinfunction "V-_7") (pintype "passive"))
    )
    (net (code "64") (name "Net-(DD8-Rs)") (class "Default")
      (node (ref "DD8") (pin "8") (pinfunction "Rs_8") (pintype "passive"))
      (node (ref "R39") (pin "1") (pinfunction "1_1") (pintype "passive"))
    )
    (net (code "65") (name "Net-(DD9-Rs)") (class "Default")
      (node (ref "DD9") (pin "8") (pinfunction "Rs_8") (pintype "passive"))
      (node (ref "R40") (pin "1") (pinfunction "1_1") (pintype "passive"))
    )
    (net (code "66") (name "Net-(DD12-ANTON)") (class "Default")
      (node (ref "DD12") (pin "14") (pinfunction "ANTON_14") (pintype "passive"))
      (node (ref "VT5") (pin "1") (pinfunction "1_1") (pintype "passive"))
    )
    (net (code "67") (name "Net-(DD12-RF_IN)") (class "Default")
      (node (ref "DD12") (pin "11") (pinfunction "RF_IN_11") (pintype "passive"))
      (node (ref "XS5") (pin "1") (pinfunction "1_1") (pintype "passive"))
    )
    (net (code "68") (name "Net-(DD12-RxD1)") (class "Default")
      (node (ref "DD12") (pin "21") (pinfunction "RxD1_21") (pintype "passive"))
      (node (ref "R62") (pin "2") (pinfunction "2_2") (pintype "passive"))
    )
    (net (code "69") (name "Net-(DD12-TIMEPULSE)") (class "Default")
      (node (ref "DD12") (pin "3") (pinfunction "TIMEPULSE_3") (pintype "passive"))
      (node (ref "R64") (pin "2") (pinfunction "2_2") (pintype "passive"))
    )
    (net (code "70") (name "Net-(DD12-TxD1)") (class "Default")
      (node (ref "DD12") (pin "20") (pinfunction "TxD1_20") (pintype "passive"))
      (node (ref "R63") (pin "2") (pinfunction "2_2") (pintype "passive"))
    )
    (net (code "71") (name "Net-(DD12-VCC)") (class "Default")
      (node (ref "C112") (pin "1") (pinfunction "1_1") (pintype "passive"))
      (node (ref "DD12") (pin "23") (pinfunction "VCC_23") (pintype "passive"))
      (node (ref "L12") (pin "2") (pinfunction "2_2") (pintype "passive"))
      (node (ref "R71") (pin "1") (pinfunction "1_1") (pintype "passive"))
    )
    (net (code "72") (name "Net-(DD12-VCC_RF)") (class "Default")
      (node (ref "DD12") (pin "9") (pinfunction "VCC_RF_9") (pintype "passive"))
      (node (ref "R72") (pin "2") (pinfunction "2_2") (pintype "passive"))
      (node (ref "VT4") (pin "2") (pinfunction "2_2") (pintype "passive"))
    )
    (net (code "73") (name "Net-(DD12-V_ANT)") (class "Default")
      (node (ref "DD12") (pin "6") (pinfunction "V_ANT_6") (pintype "passive"))
      (node (ref "R73") (pin "1") (pinfunction "1_1") (pintype "passive"))
    )
    (net (code "74") (name "Net-(DD12-V_BCKP)") (class "Default")
      (node (ref "C114") (pin "1") (pinfunction "1_1") (pintype "passive"))
      (node (ref "DD12") (pin "22") (pinfunction "V_BCKP_22") (pintype "passive"))
      (node (ref "VD13") (pin "1") (pinfunction "1_1") (pintype "passive"))
      (node (ref "VD13") (pin "2") (pinfunction "2_2") (pintype "passive"))
    )
    (net (code "75") (name "Net-(DD12-~{RESET})") (class "Default")
      (node (ref "C111") (pin "1") (pinfunction "1_1") (pintype "passive"))
      (node (ref "DD12") (pin "8") (pinfunction "~{RESET}_8") (pintype "passive"))
      (node (ref "R71") (pin "2") (pinfunction "2_2") (pintype "passive"))
    )
    (net (code "76") (name "Net-(R41-Pad2)") (class "Default")
      (node (ref "R41") (pin "2") (pinfunction "2_2") (pintype "passive"))
      (node (ref "XP3") (pin "1") (pinfunction "1_1") (pintype "passive"))
    )
    (net (code "77") (name "Net-(R42-Pad2)") (class "Default")
      (node (ref "R42") (pin "2") (pinfunction "2_2") (pintype "passive"))
      (node (ref "XP4") (pin "1") (pinfunction "1_1") (pintype "passive"))
    )
    (net (code "78") (name "Net-(R43-Pad2)") (class "Default")
      (node (ref "R43") (pin "2") (pinfunction "2_2") (pintype "passive"))
      (node (ref "XP2") (pin "1") (pinfunction "1_1") (pintype "passive"))
    )
    (net (code "79") (name "Net-(R51-Pad2)") (class "Default")
      (node (ref "R51") (pin "2") (pinfunction "2_2") (pintype "passive"))
      (node (ref "R52") (pin "2") (pinfunction "2_2") (pintype "passive"))
      (node (ref "VT1") (pin "1") (pinfunction "1_1") (pintype "passive"))
    )
    (net (code "80") (name "Net-(R53-Pad2)") (class "Default")
      (node (ref "R53") (pin "2") (pinfunction "2_2") (pintype "passive"))
      (node (ref "R61") (pin "2") (pinfunction "2_2") (pintype "passive"))
      (node (ref "VT2") (pin "1") (pinfunction "1_1") (pintype "passive"))
    )
    (net (code "81") (name "Net-(R54-Pad2)") (class "Default")
      (node (ref "R54") (pin "2") (pinfunction "2_2") (pintype "passive"))
      (node (ref "R68") (pin "2") (pinfunction "2_2") (pintype "passive"))
      (node (ref "VT3") (pin "1") (pinfunction "1_1") (pintype "passive"))
    )
    (net (code "82") (name "Net-(R55-Pad1)") (class "Default")
      (node (ref "R55") (pin "1") (pinfunction "1_1") (pintype "passive"))
      (node (ref "XS4") (pin "1") (pinfunction "1_1") (pintype "passive"))
    )
    (net (code "83") (name "Net-(R56-Pad1)") (class "Default")
      (node (ref "R56") (pin "1") (pinfunction "1_1") (pintype "passive"))
      (node (ref "XS4") (pin "2") (pinfunction "2_2") (pintype "passive"))
    )
    (net (code "84") (name "Net-(R57-Pad1)") (class "Default")
      (node (ref "R57") (pin "1") (pinfunction "1_1") (pintype "passive"))
      (node (ref "XS4") (pin "3") (pinfunction "3_3") (pintype "passive"))
    )
    (net (code "85") (name "Net-(R58-Pad1)") (class "Default")
      (node (ref "R58") (pin "1") (pinfunction "1_1") (pintype "passive"))
      (node (ref "XS4") (pin "4") (pinfunction "4_4") (pintype "passive"))
    )
    (net (code "86") (name "Net-(R67-Pad1)") (class "Default")
      (node (ref "R67") (pin "1") (pinfunction "1_1") (pintype "passive"))
      (node (ref "XP9") (pin "8") (pinfunction "8_8") (pintype "passive"))
    )
    (net (code "87") (name "Net-(R69-Pad1)") (class "Default")
      (node (ref "R69") (pin "1") (pinfunction "1_1") (pintype "passive"))
      (node (ref "XP9") (pin "7") (pinfunction "7_7") (pintype "passive"))
    )
    (net (code "88") (name "Net-(R70-Pad2)") (class "Default")
      (node (ref "R70") (pin "2") (pinfunction "2_2") (pintype "passive"))
      (node (ref "XS4") (pin "7") (pinfunction "7_7") (pintype "passive"))
    )
    (net (code "89") (name "Net-(R72-Pad1)") (class "Default")
      (node (ref "R72") (pin "1") (pinfunction "1_1") (pintype "passive"))
      (node (ref "VT4") (pin "1") (pinfunction "1_1") (pintype "passive"))
      (node (ref "VT5") (pin "3") (pinfunction "3_3") (pintype "passive"))
    )
    (net (code "90") (name "Net-(R73-Pad2)") (class "Default")
      (node (ref "R73") (pin "2") (pinfunction "2_2") (pintype "passive"))
      (node (ref "VT4") (pin "3") (pinfunction "3_3") (pintype "passive"))
    )
    (net (code "91") (name "Net-(R74-Pad1)") (class "Default")
      (node (ref "R74") (pin "1") (pinfunction "1_1") (pintype "passive"))
      (node (ref "VD13") (pin "3") (pinfunction "3_3") (pintype "passive"))
    )
    (net (code "92") (name "Net-(VD10-Pad1)") (class "Default")
      (node (ref "VD10") (pin "1") (pinfunction "1_1") (pintype "passive"))
      (node (ref "VD9") (pin "2") (pinfunction "2_2") (pintype "passive"))
      (node (ref "VT2") (pin "2") (pinfunction "2_2") (pintype "passive"))
      (node (ref "VT2") (pin "4") (pinfunction "4_4") (pintype "passive"))
      (node (ref "XP9") (pin "9") (pinfunction "9_9") (pintype "passive"))
    )
    (net (code "93") (name "Net-(VD11-Pad2)") (class "Default")
      (node (ref "VD11") (pin "2") (pinfunction "2_2") (pintype "passive"))
      (node (ref "VD12") (pin "1") (pinfunction "1_1") (pintype "passive"))
      (node (ref "VT3") (pin "2") (pinfunction "2_2") (pintype "passive"))
      (node (ref "VT3") (pin "4") (pinfunction "4_4") (pintype "passive"))
      (node (ref "XP9") (pin "10") (pinfunction "10_10") (pintype "passive"))
    )
    (net (code "94") (name "Net-(VT1-Pad2)") (class "Default")
      (node (ref "VT1") (pin "2") (pinfunction "2_2") (pintype "passive"))
      (node (ref "VT1") (pin "4") (pinfunction "4_4") (pintype "passive"))
      (node (ref "XP8") (pin "2") (pinfunction "2_2") (pintype "passive"))
    )
    (net (code "95") (name "VCC") (class "Default")
      (node (ref "C100") (pin "1") (pinfunction "1_1") (pintype "passive"))
      (node (ref "C102") (pin "1") (pinfunction "1_1") (pintype "passive"))
      (node (ref "C104") (pin "1") (pinfunction "1_1") (pintype "passive"))
      (node (ref "C105") (pin "1") (pinfunction "1_1") (pintype "passive"))
      (node (ref "C113") (pin "1") (pinfunction "1_1") (pintype "passive"))
      (node (ref "C96") (pin "1") (pinfunction "1_1") (pintype "passive"))
      (node (ref "C99") (pin "1") (pinfunction "1_1") (pintype "passive"))
      (node (ref "DD10") (pin "8") (pinfunction "VCC_8") (pintype "passive"))
      (node (ref "DD11") (pin "8") (pinfunction "Vcc_8") (pintype "passive"))
      (node (ref "DD7") (pin "12") (pinfunction "FON_12") (pintype "passive"))
      (node (ref "DD7") (pin "15") (pinfunction "VCC_15") (pintype "passive"))
      (node (ref "DD7") (pin "16") (pinfunction "~{FOF}_16") (pintype "passive"))
      (node (ref "DD8") (pin "3") (pinfunction "VCC_3") (pintype "passive"))
      (node (ref "DD9") (pin "3") (pinfunction "VCC_3") (pintype "passive"))
      (node (ref "L12") (pin "1") (pinfunction "1_1") (pintype "passive"))
      (node (ref "R44") (pin "1") (pinfunction "1_1") (pintype "passive"))
      (node (ref "R46") (pin "1") (pinfunction "1_1") (pintype "passive"))
      (node (ref "R47") (pin "1") (pinfunction "1_1") (pintype "passive"))
      (node (ref "R48") (pin "1") (pinfunction "1_1") (pintype "passive"))
      (node (ref "R49") (pin "1") (pinfunction "1_1") (pintype "passive"))
      (node (ref "R50") (pin "1") (pinfunction "1_1") (pintype "passive"))
      (node (ref "R70") (pin "1") (pinfunction "1_1") (pintype "passive"))
      (node (ref "R74") (pin "2") (pinfunction "2_2") (pintype "passive"))
      (node (ref "VD7") (pin "2") (pinfunction "2_2") (pintype "passive"))
      (node (ref "VD8") (pin "2") (pinfunction "2_2") (pintype "passive"))
      (node (ref "XP5") (pin "1") (pinfunction "1_1") (pintype "passive"))
    )
    (net (code "96") (name "VDD_5V") (class "Default")
      (node (ref "XP1") (pin "1") (pinfunction "1_1") (pintype "passive"))
    )
    (net (code "97") (name "unconnected-(DD7-~{INV}-Pad10)") (class "Default")
      (node (ref "DD7") (pin "10") (pinfunction "~{INV}_10") (pintype "passive"))
    )
    (net (code "98") (name "unconnected-(DD11-OS-Pad3)") (class "Default")
      (node (ref "DD11") (pin "3") (pinfunction "OS_3") (pintype "passive"))
    )
    (net (code "99") (name "unconnected-(DD12-~{AADET}-Pad5)") (class "Default")
      (node (ref "DD12") (pin "5") (pinfunction "~{AADET}_5") (pintype "passive"))
    )
  )
)
